# Schematic.net
KiCad netlist of a schematic drawn in EasyEDA
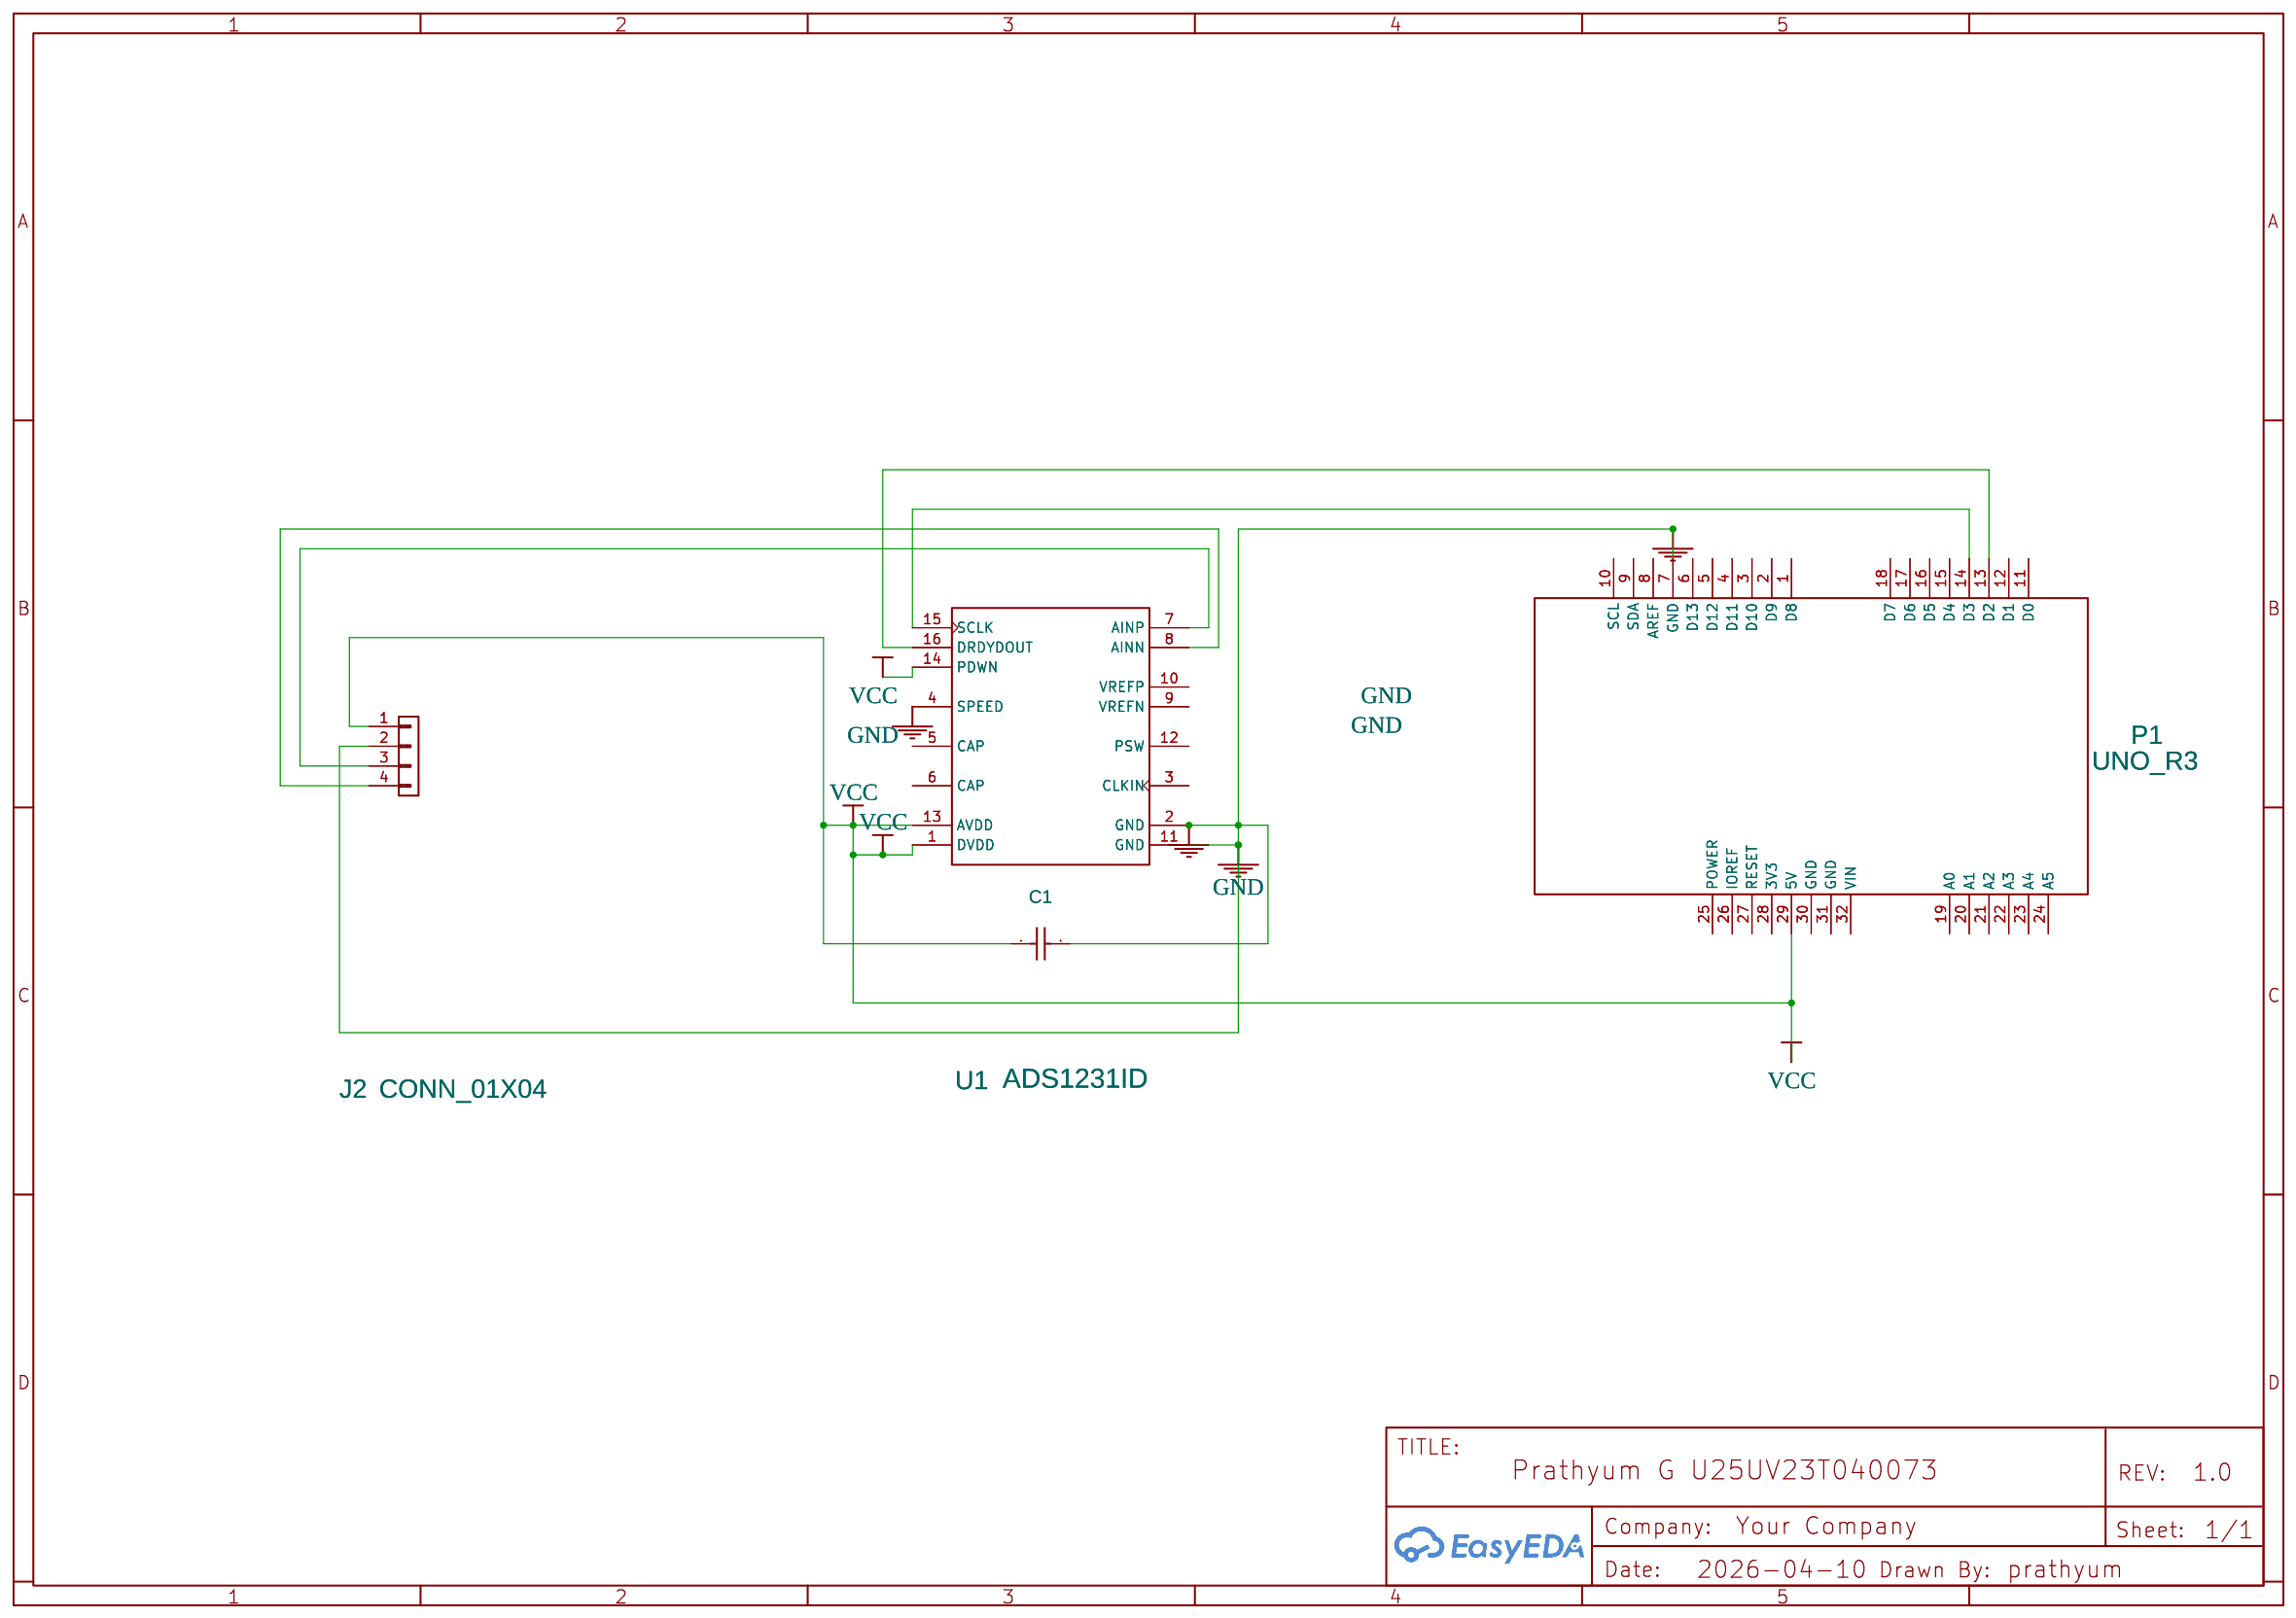
[diagram p0: schematic sheet]

(export (version "E")
  (design (tool "Eeschema 10.0.6"))
  (components
    (comp (ref "C1")
      (value "100nF")
      (fields (field (name "Manufacturer Part") "104J 40OV") (field (name "Manufacturer") "ReliaPro"))
      (libsource (lib "") (part "104J 40OV"))
    )
    (comp (ref "J2") (value "CONN_01X04") (libsource (lib "") (part "CONN_01X04")))
    (comp (ref "P1") (value "UNO_R3") (libsource (lib "") (part "UNO_R3")))
    (comp (ref "U1") (value "ADS1231ID") (libsource (lib "") (part "ADS1231ID")))
  )
  (nets
    (net (code "1") (name "GND") (class "Default")
      (node (ref "C1") (pin "2") (pinfunction "2_2") (pintype "input"))
      (node (ref "J2") (pin "2") (pinfunction "P2_2") (pintype "unspecified"))
      (node (ref "P1") (pin "7") (pinfunction "GND_7") (pintype "unspecified"))
      (node (ref "U1") (pin "11") (pinfunction "GND_11") (pintype "passive"))
      (node (ref "U1") (pin "2") (pinfunction "GND_2") (pintype "passive"))
      (node (ref "U1") (pin "4") (pinfunction "SPEED_4") (pintype "unspecified"))
    )
    (net (code "2") (name "Net-(J2-P3)") (class "Default")
      (node (ref "J2") (pin "3") (pinfunction "P3_3") (pintype "unspecified"))
      (node (ref "U1") (pin "7") (pinfunction "AINP_7") (pintype "unspecified"))
    )
    (net (code "3") (name "Net-(J2-P4)") (class "Default")
      (node (ref "J2") (pin "4") (pinfunction "P4_4") (pintype "unspecified"))
      (node (ref "U1") (pin "8") (pinfunction "AINN_8") (pintype "unspecified"))
    )
    (net (code "4") (name "Net-(P1-D2)") (class "Default")
      (node (ref "P1") (pin "13") (pinfunction "D2_13") (pintype "unspecified"))
      (node (ref "U1") (pin "16") (pinfunction "DRDYDOUT_16") (pintype "output"))
    )
    (net (code "5") (name "Net-(P1-D3)") (class "Default")
      (node (ref "P1") (pin "14") (pinfunction "D3_14") (pintype "unspecified"))
      (node (ref "U1") (pin "15") (pinfunction "SCLK_15") (pintype "unspecified"))
    )
    (net (code "6") (name "VCC") (class "Default")
      (node (ref "C1") (pin "1") (pinfunction "1_1") (pintype "input"))
      (node (ref "J2") (pin "1") (pinfunction "P1_1") (pintype "unspecified"))
      (node (ref "P1") (pin "29") (pinfunction "5V_29") (pintype "unspecified"))
      (node (ref "U1") (pin "1") (pinfunction "DVDD_1") (pintype "passive"))
      (node (ref "U1") (pin "13") (pinfunction "AVDD_13") (pintype "passive"))
      (node (ref "U1") (pin "14") (pinfunction "PDWN_14") (pintype "unspecified"))
    )
    (net (code "7") (name "unconnected-(P1-3V3-Pad28)") (class "Default")
      (node (ref "P1") (pin "28") (pinfunction "3V3_28") (pintype "unspecified"))
    )
    (net (code "8") (name "unconnected-(P1-A0-Pad19)") (class "Default")
      (node (ref "P1") (pin "19") (pinfunction "A0_19") (pintype "unspecified"))
    )
    (net (code "9") (name "unconnected-(P1-A1-Pad20)") (class "Default")
      (node (ref "P1") (pin "20") (pinfunction "A1_20") (pintype "unspecified"))
    )
    (net (code "10") (name "unconnected-(P1-A2-Pad21)") (class "Default")
      (node (ref "P1") (pin "21") (pinfunction "A2_21") (pintype "unspecified"))
    )
    (net (code "11") (name "unconnected-(P1-A3-Pad22)") (class "Default")
      (node (ref "P1") (pin "22") (pinfunction "A3_22") (pintype "unspecified"))
    )
    (net (code "12") (name "unconnected-(P1-A4-Pad23)") (class "Default")
      (node (ref "P1") (pin "23") (pinfunction "A4_23") (pintype "unspecified"))
    )
    (net (code "13") (name "unconnected-(P1-A5-Pad24)") (class "Default")
      (node (ref "P1") (pin "24") (pinfunction "A5_24") (pintype "unspecified"))
    )
    (net (code "14") (name "unconnected-(P1-AREF-Pad8)") (class "Default")
      (node (ref "P1") (pin "8") (pinfunction "AREF_8") (pintype "unspecified"))
    )
    (net (code "15") (name "unconnected-(P1-D0-Pad11)") (class "Default")
      (node (ref "P1") (pin "11") (pinfunction "D0_11") (pintype "unspecified"))
    )
    (net (code "16") (name "unconnected-(P1-D1-Pad12)") (class "Default")
      (node (ref "P1") (pin "12") (pinfunction "D1_12") (pintype "unspecified"))
    )
    (net (code "17") (name "unconnected-(P1-D4-Pad15)") (class "Default")
      (node (ref "P1") (pin "15") (pinfunction "D4_15") (pintype "unspecified"))
    )
    (net (code "18") (name "unconnected-(P1-D5-Pad16)") (class "Default")
      (node (ref "P1") (pin "16") (pinfunction "D5_16") (pintype "unspecified"))
    )
    (net (code "19") (name "unconnected-(P1-D6-Pad17)") (class "Default")
      (node (ref "P1") (pin "17") (pinfunction "D6_17") (pintype "unspecified"))
    )
    (net (code "20") (name "unconnected-(P1-D7-Pad18)") (class "Default")
      (node (ref "P1") (pin "18") (pinfunction "D7_18") (pintype "unspecified"))
    )
    (net (code "21") (name "unconnected-(P1-D8-Pad1)") (class "Default")
      (node (ref "P1") (pin "1") (pinfunction "D8_1") (pintype "unspecified"))
    )
    (net (code "22") (name "unconnected-(P1-D9-Pad2)") (class "Default")
      (node (ref "P1") (pin "2") (pinfunction "D9_2") (pintype "unspecified"))
    )
    (net (code "23") (name "unconnected-(P1-D10-Pad3)") (class "Default")
      (node (ref "P1") (pin "3") (pinfunction "D10_3") (pintype "unspecified"))
    )
    (net (code "24") (name "unconnected-(P1-D11-Pad4)") (class "Default")
      (node (ref "P1") (pin "4") (pinfunction "D11_4") (pintype "unspecified"))
    )
    (net (code "25") (name "unconnected-(P1-D12-Pad5)") (class "Default")
      (node (ref "P1") (pin "5") (pinfunction "D12_5") (pintype "unspecified"))
    )
    (net (code "26") (name "unconnected-(P1-D13-Pad6)") (class "Default")
      (node (ref "P1") (pin "6") (pinfunction "D13_6") (pintype "unspecified"))
    )
    (net (code "27") (name "unconnected-(P1-GND-Pad30)") (class "Default")
      (node (ref "P1") (pin "30") (pinfunction "GND_30") (pintype "unspecified"))
    )
    (net (code "28") (name "unconnected-(P1-GND-Pad31)") (class "Default")
      (node (ref "P1") (pin "31") (pinfunction "GND_31") (pintype "unspecified"))
    )
    (net (code "29") (name "unconnected-(P1-IOREF-Pad26)") (class "Default")
      (node (ref "P1") (pin "26") (pinfunction "IOREF_26") (pintype "unspecified"))
    )
    (net (code "30") (name "unconnected-(P1-POWER-Pad25)") (class "Default")
      (node (ref "P1") (pin "25") (pinfunction "POWER_25") (pintype "unspecified"))
    )
    (net (code "31") (name "unconnected-(P1-RESET-Pad27)") (class "Default")
      (node (ref "P1") (pin "27") (pinfunction "RESET_27") (pintype "unspecified"))
    )
    (net (code "32") (name "unconnected-(P1-SCL-Pad10)") (class "Default")
      (node (ref "P1") (pin "10") (pinfunction "SCL_10") (pintype "unspecified"))
    )
    (net (code "33") (name "unconnected-(P1-SDA-Pad9)") (class "Default")
      (node (ref "P1") (pin "9") (pinfunction "SDA_9") (pintype "unspecified"))
    )
    (net (code "34") (name "unconnected-(P1-VIN-Pad32)") (class "Default")
      (node (ref "P1") (pin "32") (pinfunction "VIN_32") (pintype "unspecified"))
    )
    (net (code "35") (name "unconnected-(U1-CAP-Pad5)") (class "Default")
      (node (ref "U1") (pin "5") (pinfunction "CAP_5") (pintype "unspecified"))
    )
    (net (code "36") (name "unconnected-(U1-CAP-Pad6)") (class "Default")
      (node (ref "U1") (pin "6") (pinfunction "CAP_6") (pintype "unspecified"))
    )
    (net (code "37") (name "unconnected-(U1-CLKIN-Pad3)") (class "Default")
      (node (ref "U1") (pin "3") (pinfunction "CLKIN_3") (pintype "unspecified"))
    )
    (net (code "38") (name "unconnected-(U1-PSW-Pad12)") (class "Default")
      (node (ref "U1") (pin "12") (pinfunction "PSW_12") (pintype "passive"))
    )
    (net (code "39") (name "unconnected-(U1-VREFN-Pad9)") (class "Default")
      (node (ref "U1") (pin "9") (pinfunction "VREFN_9") (pintype "unspecified"))
    )
    (net (code "40") (name "unconnected-(U1-VREFP-Pad10)") (class "Default")
      (node (ref "U1") (pin "10") (pinfunction "VREFP_10") (pintype "unspecified"))
    )
  )
)
